# special-channel-selection.net
KiCad netlist of a schematic drawn in Altium Designer
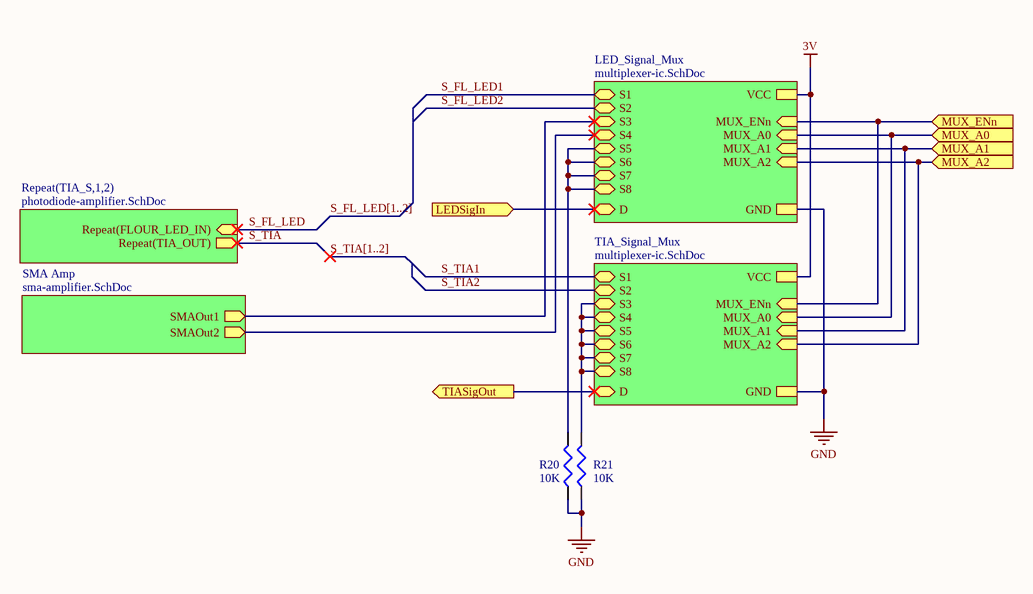
[diagram p0: special-channel-selection.SchDoc]

(export (version "E")
  (design (tool "Eeschema 10.0.6"))
  (components
    (comp (ref "R20")
      (value "10K")
      (footprint "0402")
      (description "Resistor")
      (fields (field (name "PUBLISHER") "Altium Limited"))
      (libsource (lib "Miscellaneous Devices") (part "Res3"))
    )
    (comp (ref "R21")
      (value "10K")
      (footprint "0402")
      (description "Resistor")
      (fields (field (name "PUBLISHER") "Altium Limited"))
      (libsource (lib "Miscellaneous Devices") (part "Res3"))
    )
  )
  (nets
    (net (code "6") (name "/S3") (class "Default")
      (node (ref "R21") (pin "2") (pinfunction "2_2") (pintype "passive"))
    )
    (net (code "7") (name "/S5") (class "Default")
      (node (ref "R20") (pin "2") (pinfunction "2_2") (pintype "passive"))
    )
    (net (code "20") (name "GND") (class "Default")
      (node (ref "R20") (pin "1") (pinfunction "1_1") (pintype "passive"))
      (node (ref "R21") (pin "1") (pinfunction "1_1") (pintype "passive"))
    )
  )
)
